# Output1-12.net
KiCad netlist of a schematic drawn in Altium Designer
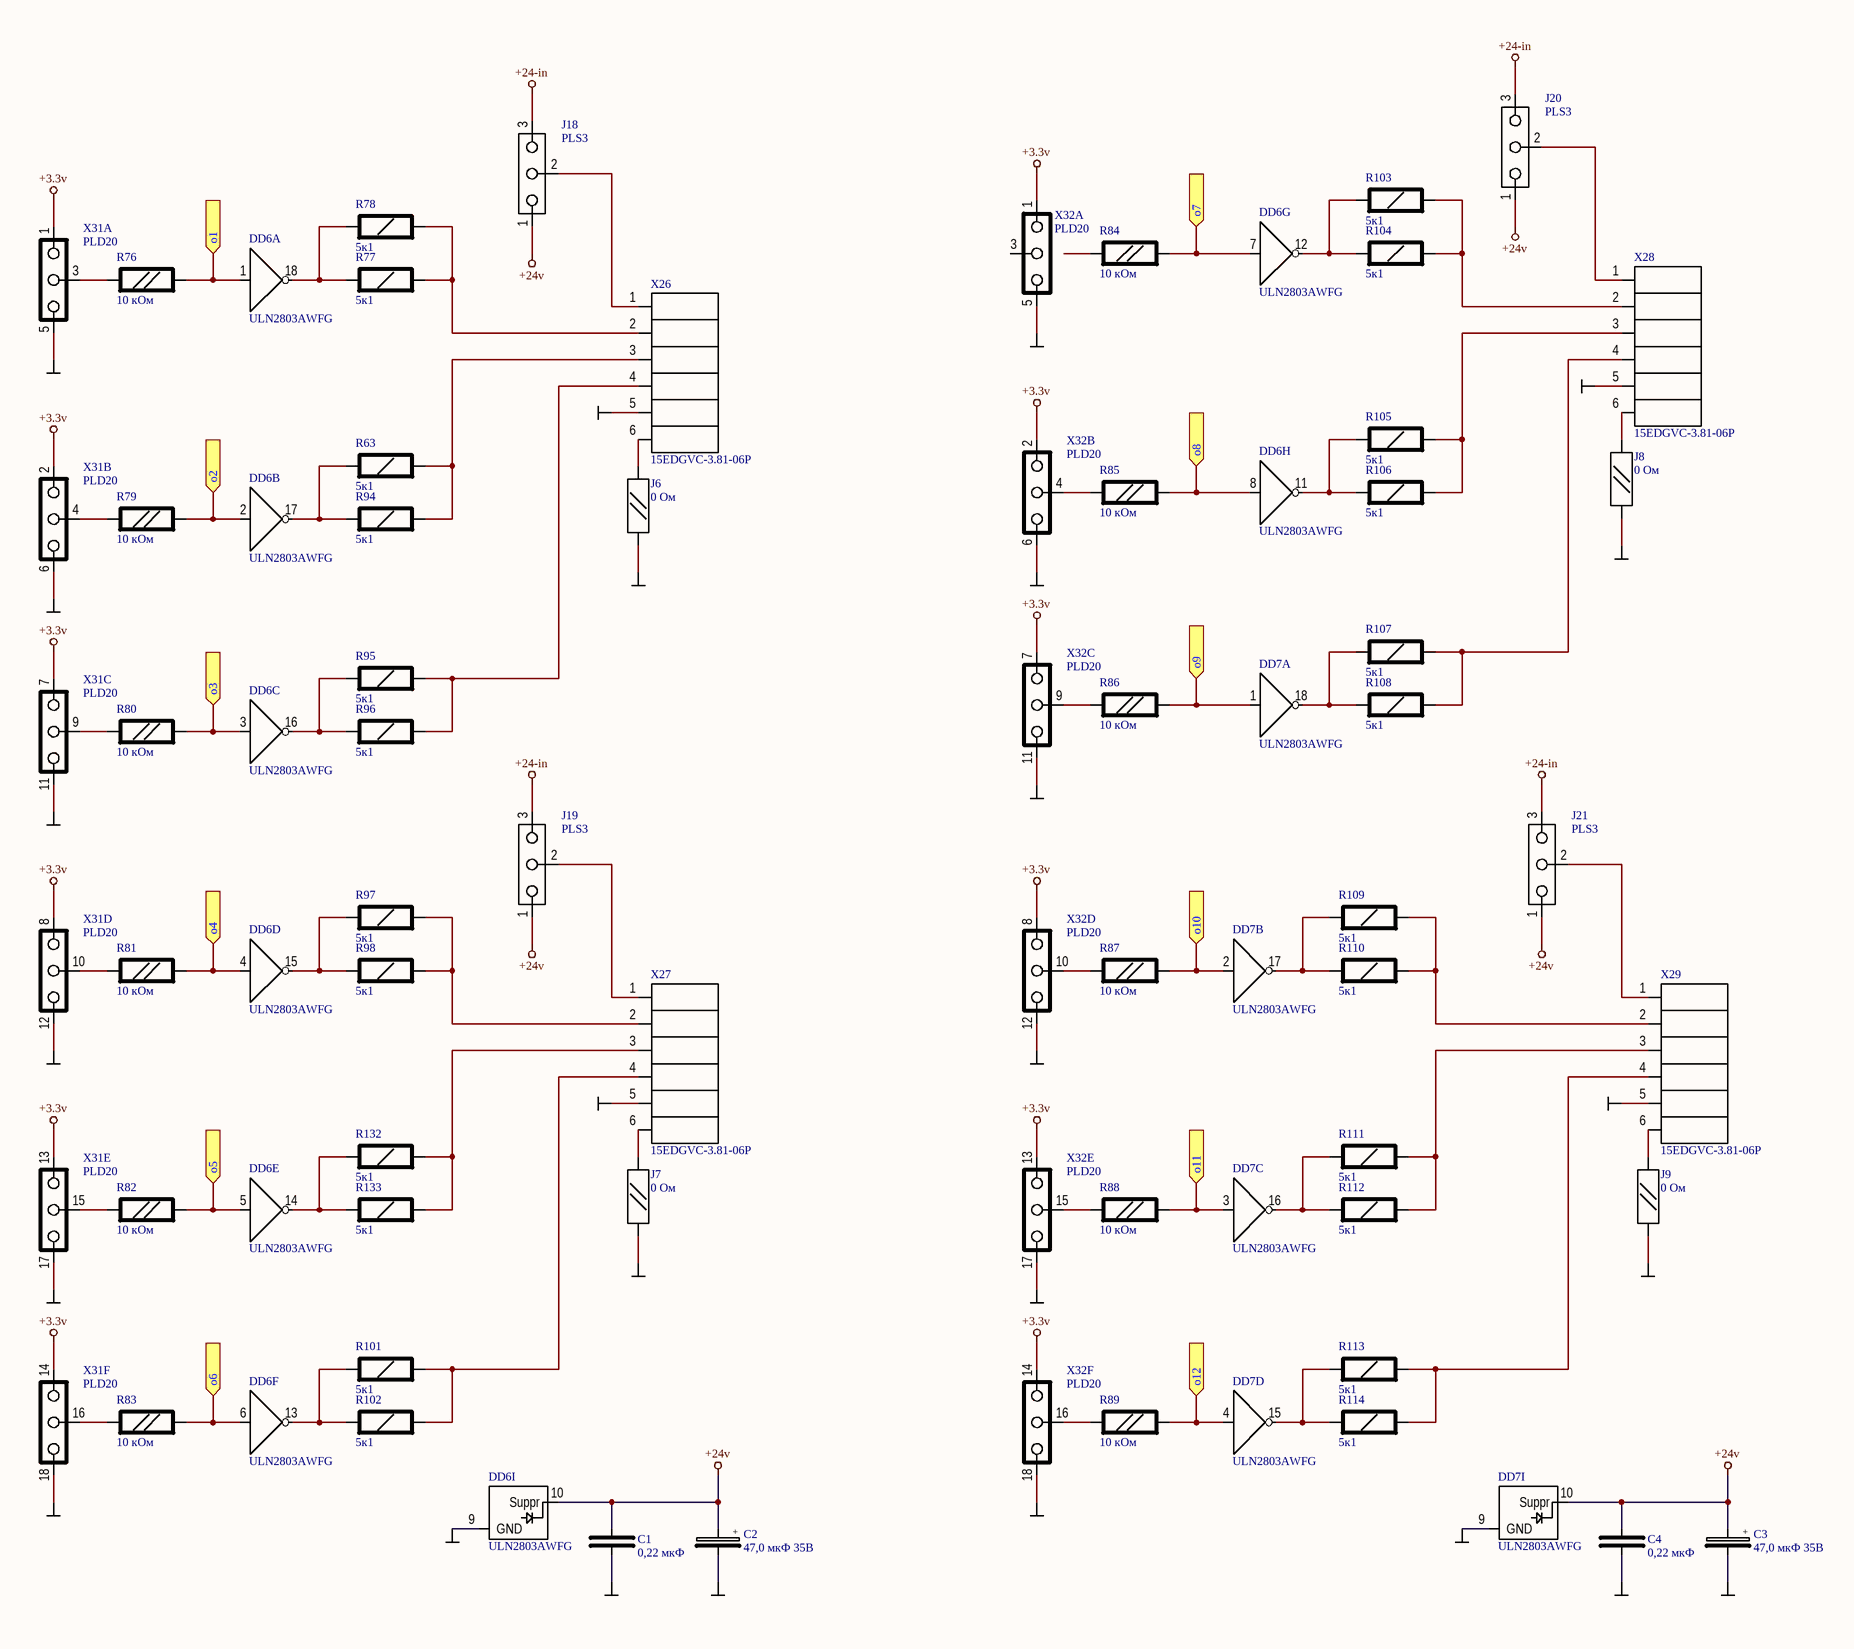
[diagram p0: Output1-12.SchDoc]

(export (version "E")
  (design (tool "Eeschema 10.0.6"))
  (components
    (comp (ref "C1")
      (value "0,22 мкФ")
      (footprint "SMD0805CAP")
      (description "Чип конденсатор 0805")
      (fields (field (name "VOLTAGE") "50V"))
      (libsource (lib "SL02_22F") (part "C0805"))
    )
    (comp (ref "C2")
      (value "47,0 мкФ 35В")
      (footprint "cap6")
      (description "5мм Электролитический конденсатор")
      (libsource (lib "SL02_22F") (part "C_e"))
    )
    (comp (ref "C3")
      (value "47,0 мкФ 35В")
      (footprint "cap6")
      (description "5мм Электролитический конденсатор")
      (libsource (lib "SL02_22F") (part "C_e"))
    )
    (comp (ref "C4")
      (value "0,22 мкФ")
      (footprint "SMD0805CAP")
      (description "Чип конденсатор 0805")
      (fields (field (name "VOLTAGE") "50V"))
      (libsource (lib "SL02_22F") (part "C0805"))
    )
    (comp (ref "DD6")
      (value "ULN2803AWFG")
      (footprint "SOL18")
      (description "Буфер 8-канальный")
      (fields (field (name "VOLTAGE") "50V"))
      (libsource (lib "SL02_22F") (part "ULN2803"))
    )
    (comp (ref "DD7")
      (value "ULN2803AWFG")
      (footprint "SOL18")
      (description "Буфер 8-канальный")
      (fields (field (name "VOLTAGE") "50V"))
      (libsource (lib "SL02_22F") (part "ULN2803"))
    )
    (comp (ref "J6")
      (value "0 Ом")
      (footprint "SMD0805RES")
      (description "SMD 0805 перемычка")
      (libsource (lib "L02_22F") (part "JR0805"))
    )
    (comp (ref "J7")
      (value "0 Ом")
      (footprint "SMD0805RES")
      (description "SMD 0805 перемычка")
      (libsource (lib "L02_22F") (part "JR0805"))
    )
    (comp (ref "J8")
      (value "0 Ом")
      (footprint "SMD0805RES")
      (description "SMD 0805 перемычка")
      (libsource (lib "L02_22F") (part "JR0805"))
    )
    (comp (ref "J9")
      (value "0 Ом")
      (footprint "SMD0805RES")
      (description "SMD 0805 перемычка")
      (libsource (lib "L02_22F") (part "JR0805"))
    )
    (comp (ref "J18")
      (value "PLS3")
      (footprint "HDR1X3")
      (description "Джампер PLS3 2.54мм")
      (libsource (lib "L02_22F") (part "PLS3"))
    )
    (comp (ref "J19")
      (value "PLS3")
      (footprint "HDR1X3")
      (description "Джампер PLS3 2.54мм")
      (libsource (lib "L02_22F") (part "PLS3"))
    )
    (comp (ref "J20")
      (value "PLS3")
      (footprint "HDR1X3")
      (description "Джампер PLS3 2.54мм")
      (libsource (lib "L02_22F") (part "PLS3"))
    )
    (comp (ref "J21")
      (value "PLS3")
      (footprint "HDR1X3")
      (description "Джампер PLS3 2.54мм")
      (libsource (lib "L02_22F") (part "PLS3"))
    )
    (comp (ref "R63")
      (value "5к1")
      (footprint "RES1206")
      (description "Чип резистор 1206")
      (fields (field (name "TOLERANCE") "5%"))
      (libsource (lib "SL02_22F") (part "R1206"))
    )
    (comp (ref "R76")
      (value "10 кОм")
      (footprint "SMD0805RES")
      (description "Чип резистор 0805")
      (fields (field (name "TOLERANCE") "5%"))
      (libsource (lib "SL02_22F") (part "R0805"))
    )
    (comp (ref "R77")
      (value "5к1")
      (footprint "RES1206")
      (description "Чип резистор 1206")
      (fields (field (name "TOLERANCE") "5%"))
      (libsource (lib "SL02_22F") (part "R1206"))
    )
    (comp (ref "R78")
      (value "5к1")
      (footprint "RES1206")
      (description "Чип резистор 1206")
      (fields (field (name "TOLERANCE") "5%"))
      (libsource (lib "SL02_22F") (part "R1206"))
    )
    (comp (ref "R79")
      (value "10 кОм")
      (footprint "SMD0805RES")
      (description "Чип резистор 0805")
      (fields (field (name "TOLERANCE") "5%"))
      (libsource (lib "SL02_22F") (part "R0805"))
    )
    (comp (ref "R80")
      (value "10 кОм")
      (footprint "SMD0805RES")
      (description "Чип резистор 0805")
      (fields (field (name "TOLERANCE") "5%"))
      (libsource (lib "SL02_22F") (part "R0805"))
    )
    (comp (ref "R81")
      (value "10 кОм")
      (footprint "SMD0805RES")
      (description "Чип резистор 0805")
      (fields (field (name "TOLERANCE") "5%"))
      (libsource (lib "SL02_22F") (part "R0805"))
    )
    (comp (ref "R82")
      (value "10 кОм")
      (footprint "SMD0805RES")
      (description "Чип резистор 0805")
      (fields (field (name "TOLERANCE") "5%"))
      (libsource (lib "SL02_22F") (part "R0805"))
    )
    (comp (ref "R83")
      (value "10 кОм")
      (footprint "SMD0805RES")
      (description "Чип резистор 0805")
      (fields (field (name "TOLERANCE") "5%"))
      (libsource (lib "SL02_22F") (part "R0805"))
    )
    (comp (ref "R84")
      (value "10 кОм")
      (footprint "SMD0805RES")
      (description "Чип резистор 0805")
      (fields (field (name "TOLERANCE") "5%"))
      (libsource (lib "SL02_22F") (part "R0805"))
    )
    (comp (ref "R85")
      (value "10 кОм")
      (footprint "SMD0805RES")
      (description "Чип резистор 0805")
      (fields (field (name "TOLERANCE") "5%"))
      (libsource (lib "SL02_22F") (part "R0805"))
    )
    (comp (ref "R86")
      (value "10 кОм")
      (footprint "SMD0805RES")
      (description "Чип резистор 0805")
      (fields (field (name "TOLERANCE") "5%"))
      (libsource (lib "SL02_22F") (part "R0805"))
    )
    (comp (ref "R87")
      (value "10 кОм")
      (footprint "SMD0805RES")
      (description "Чип резистор 0805")
      (fields (field (name "TOLERANCE") "5%"))
      (libsource (lib "SL02_22F") (part "R0805"))
    )
    (comp (ref "R88")
      (value "10 кОм")
      (footprint "SMD0805RES")
      (description "Чип резистор 0805")
      (fields (field (name "TOLERANCE") "5%"))
      (libsource (lib "SL02_22F") (part "R0805"))
    )
    (comp (ref "R89")
      (value "10 кОм")
      (footprint "SMD0805RES")
      (description "Чип резистор 0805")
      (fields (field (name "TOLERANCE") "5%"))
      (libsource (lib "SL02_22F") (part "R0805"))
    )
    (comp (ref "R94")
      (value "5к1")
      (footprint "RES1206")
      (description "Чип резистор 1206")
      (fields (field (name "TOLERANCE") "5%"))
      (libsource (lib "SL02_22F") (part "R1206"))
    )
    (comp (ref "R95")
      (value "5к1")
      (footprint "RES1206")
      (description "Чип резистор 1206")
      (fields (field (name "TOLERANCE") "5%"))
      (libsource (lib "SL02_22F") (part "R1206"))
    )
    (comp (ref "R96")
      (value "5к1")
      (footprint "RES1206")
      (description "Чип резистор 1206")
      (fields (field (name "TOLERANCE") "5%"))
      (libsource (lib "SL02_22F") (part "R1206"))
    )
    (comp (ref "R97")
      (value "5к1")
      (footprint "RES1206")
      (description "Чип резистор 1206")
      (fields (field (name "TOLERANCE") "5%"))
      (libsource (lib "SL02_22F") (part "R1206"))
    )
    (comp (ref "R98")
      (value "5к1")
      (footprint "RES1206")
      (description "Чип резистор 1206")
      (fields (field (name "TOLERANCE") "5%"))
      (libsource (lib "SL02_22F") (part "R1206"))
    )
    (comp (ref "R101")
      (value "5к1")
      (footprint "RES1206")
      (description "Чип резистор 1206")
      (fields (field (name "TOLERANCE") "5%"))
      (libsource (lib "SL02_22F") (part "R1206"))
    )
    (comp (ref "R102")
      (value "5к1")
      (footprint "RES1206")
      (description "Чип резистор 1206")
      (fields (field (name "TOLERANCE") "5%"))
      (libsource (lib "SL02_22F") (part "R1206"))
    )
    (comp (ref "R103")
      (value "5к1")
      (footprint "RES1206")
      (description "Чип резистор 1206")
      (fields (field (name "TOLERANCE") "5%"))
      (libsource (lib "SL02_22F") (part "R1206"))
    )
    (comp (ref "R104")
      (value "5к1")
      (footprint "RES1206")
      (description "Чип резистор 1206")
      (fields (field (name "TOLERANCE") "5%"))
      (libsource (lib "SL02_22F") (part "R1206"))
    )
    (comp (ref "R105")
      (value "5к1")
      (footprint "RES1206")
      (description "Чип резистор 1206")
      (fields (field (name "TOLERANCE") "5%"))
      (libsource (lib "SL02_22F") (part "R1206"))
    )
    (comp (ref "R106")
      (value "5к1")
      (footprint "RES1206")
      (description "Чип резистор 1206")
      (fields (field (name "TOLERANCE") "5%"))
      (libsource (lib "SL02_22F") (part "R1206"))
    )
    (comp (ref "R107")
      (value "5к1")
      (footprint "RES1206")
      (description "Чип резистор 1206")
      (fields (field (name "TOLERANCE") "5%"))
      (libsource (lib "SL02_22F") (part "R1206"))
    )
    (comp (ref "R108")
      (value "5к1")
      (footprint "RES1206")
      (description "Чип резистор 1206")
      (fields (field (name "TOLERANCE") "5%"))
      (libsource (lib "SL02_22F") (part "R1206"))
    )
    (comp (ref "R109")
      (value "5к1")
      (footprint "RES1206")
      (description "Чип резистор 1206")
      (fields (field (name "TOLERANCE") "5%"))
      (libsource (lib "SL02_22F") (part "R1206"))
    )
    (comp (ref "R110")
      (value "5к1")
      (footprint "RES1206")
      (description "Чип резистор 1206")
      (fields (field (name "TOLERANCE") "5%"))
      (libsource (lib "SL02_22F") (part "R1206"))
    )
    (comp (ref "R111")
      (value "5к1")
      (footprint "RES1206")
      (description "Чип резистор 1206")
      (fields (field (name "TOLERANCE") "5%"))
      (libsource (lib "SL02_22F") (part "R1206"))
    )
    (comp (ref "R112")
      (value "5к1")
      (footprint "RES1206")
      (description "Чип резистор 1206")
      (fields (field (name "TOLERANCE") "5%"))
      (libsource (lib "SL02_22F") (part "R1206"))
    )
    (comp (ref "R113")
      (value "5к1")
      (footprint "RES1206")
      (description "Чип резистор 1206")
      (fields (field (name "TOLERANCE") "5%"))
      (libsource (lib "SL02_22F") (part "R1206"))
    )
    (comp (ref "R114")
      (value "5к1")
      (footprint "RES1206")
      (description "Чип резистор 1206")
      (fields (field (name "TOLERANCE") "5%"))
      (libsource (lib "SL02_22F") (part "R1206"))
    )
    (comp (ref "R132")
      (value "5к1")
      (footprint "RES1206")
      (description "Чип резистор 1206")
      (fields (field (name "TOLERANCE") "5%"))
      (libsource (lib "SL02_22F") (part "R1206"))
    )
    (comp (ref "R133")
      (value "5к1")
      (footprint "RES1206")
      (description "Чип резистор 1206")
      (fields (field (name "TOLERANCE") "5%"))
      (libsource (lib "SL02_22F") (part "R1206"))
    )
    (comp (ref "X26")
      (value "15EDGVC-3.81-06P")
      (footprint "15EDGVC_081_6")
      (description "Вилка  6/3.81")
      (fields (field (name "VOLTAGE") "2кВ"))
      (libsource (lib "L02_22F") (part "15EDGVC-3.81-06P"))
    )
    (comp (ref "X27")
      (value "15EDGVC-3.81-06P")
      (footprint "15EDGVC_081_6")
      (description "Вилка  6/3.81")
      (fields (field (name "VOLTAGE") "2кВ"))
      (libsource (lib "L02_22F") (part "15EDGVC-3.81-06P"))
    )
    (comp (ref "X28")
      (value "15EDGVC-3.81-06P")
      (footprint "15EDGVC_081_6")
      (description "Вилка  6/3.81")
      (fields (field (name "VOLTAGE") "2кВ"))
      (libsource (lib "L02_22F") (part "15EDGVC-3.81-06P"))
    )
    (comp (ref "X29")
      (value "15EDGVC-3.81-06P")
      (footprint "15EDGVC_081_6")
      (description "Вилка  6/3.81")
      (fields (field (name "VOLTAGE") "2кВ"))
      (libsource (lib "L02_22F") (part "15EDGVC-3.81-06P"))
    )
    (comp (ref "X31")
      (value "PLD20")
      (footprint "pld2x10_1.27")
      (description "Вилка  PLD 20/1.27")
      (libsource (lib "") (part "PLD20_2"))
    )
    (comp (ref "X32")
      (value "PLD20")
      (footprint "pld2x10_1.27")
      (description "Вилка  PLD 20/1.27")
      (libsource (lib "") (part "PLD20_1"))
    )
  )
  (nets
    (net (code "1") (name "+3.3v") (class "Default")
      (node (ref "X31") (pin "1") (pinfunction "1_1") (pintype "passive"))
      (node (ref "X31") (pin "13") (pinfunction "13_13") (pintype "passive"))
      (node (ref "X31") (pin "14") (pinfunction "14_14") (pintype "passive"))
      (node (ref "X31") (pin "2") (pinfunction "2_2") (pintype "passive"))
      (node (ref "X31") (pin "7") (pinfunction "7_7") (pintype "passive"))
      (node (ref "X31") (pin "8") (pinfunction "8_8") (pintype "passive"))
      (node (ref "X32") (pin "1") (pinfunction "1_1") (pintype "passive"))
      (node (ref "X32") (pin "13") (pinfunction "13_13") (pintype "passive"))
      (node (ref "X32") (pin "14") (pinfunction "14_14") (pintype "passive"))
      (node (ref "X32") (pin "2") (pinfunction "2_2") (pintype "passive"))
      (node (ref "X32") (pin "7") (pinfunction "7_7") (pintype "passive"))
      (node (ref "X32") (pin "8") (pinfunction "8_8") (pintype "passive"))
    )
    (net (code "2") (name "+24-in") (class "Default")
      (node (ref "J18") (pin "3") (pinfunction "Left_3") (pintype "passive"))
      (node (ref "J19") (pin "3") (pinfunction "Left_3") (pintype "passive"))
      (node (ref "J20") (pin "3") (pinfunction "Left_3") (pintype "passive"))
      (node (ref "J21") (pin "3") (pinfunction "Left_3") (pintype "passive"))
    )
    (net (code "3") (name "+24v") (class "Default")
      (node (ref "C1") (pin "1") (pinfunction "1_1") (pintype "passive"))
      (node (ref "C2") (pin "1") (pinfunction "+_1") (pintype "passive"))
      (node (ref "C3") (pin "1") (pinfunction "+_1") (pintype "passive"))
      (node (ref "C4") (pin "1") (pinfunction "1_1") (pintype "passive"))
      (node (ref "DD6") (pin "10") (pinfunction "Suppr_10") (pintype "passive"))
      (node (ref "DD7") (pin "10") (pinfunction "Suppr_10") (pintype "passive"))
      (node (ref "J18") (pin "1") (pinfunction "Right_1") (pintype "passive"))
      (node (ref "J19") (pin "1") (pinfunction "Right_1") (pintype "passive"))
      (node (ref "J20") (pin "1") (pinfunction "Right_1") (pintype "passive"))
      (node (ref "J21") (pin "1") (pinfunction "Right_1") (pintype "passive"))
    )
    (net (code "4") (name "/o1") (class "Default")
      (node (ref "DD6") (pin "1") (pinfunction "In_1") (pintype "input"))
      (node (ref "R76") (pin "1") (pinfunction "1_1") (pintype "passive"))
    )
    (net (code "5") (name "/o2") (class "Default")
      (node (ref "DD6") (pin "2") (pinfunction "In_2") (pintype "input"))
      (node (ref "R79") (pin "1") (pinfunction "1_1") (pintype "passive"))
    )
    (net (code "6") (name "/o3") (class "Default")
      (node (ref "DD6") (pin "3") (pinfunction "In_3") (pintype "input"))
      (node (ref "R80") (pin "1") (pinfunction "1_1") (pintype "passive"))
    )
    (net (code "7") (name "/o4") (class "Default")
      (node (ref "DD6") (pin "4") (pinfunction "In_4") (pintype "input"))
      (node (ref "R81") (pin "1") (pinfunction "1_1") (pintype "passive"))
    )
    (net (code "8") (name "/o5") (class "Default")
      (node (ref "DD6") (pin "5") (pinfunction "In_5") (pintype "input"))
      (node (ref "R82") (pin "1") (pinfunction "1_1") (pintype "passive"))
    )
    (net (code "9") (name "/o6") (class "Default")
      (node (ref "DD6") (pin "6") (pinfunction "In_6") (pintype "input"))
      (node (ref "R83") (pin "1") (pinfunction "1_1") (pintype "passive"))
    )
    (net (code "10") (name "/o7") (class "Default")
      (node (ref "DD6") (pin "7") (pinfunction "In_7") (pintype "input"))
      (node (ref "R84") (pin "1") (pinfunction "1_1") (pintype "passive"))
    )
    (net (code "11") (name "/o8") (class "Default")
      (node (ref "DD6") (pin "8") (pinfunction "In_8") (pintype "input"))
      (node (ref "R85") (pin "1") (pinfunction "1_1") (pintype "passive"))
    )
    (net (code "12") (name "/o9") (class "Default")
      (node (ref "DD7") (pin "1") (pinfunction "In_1") (pintype "input"))
      (node (ref "R86") (pin "1") (pinfunction "1_1") (pintype "passive"))
    )
    (net (code "13") (name "/o10") (class "Default")
      (node (ref "DD7") (pin "2") (pinfunction "In_2") (pintype "input"))
      (node (ref "R87") (pin "1") (pinfunction "1_1") (pintype "passive"))
    )
    (net (code "14") (name "/o11") (class "Default")
      (node (ref "DD7") (pin "3") (pinfunction "In_3") (pintype "input"))
      (node (ref "R88") (pin "1") (pinfunction "1_1") (pintype "passive"))
    )
    (net (code "15") (name "/o12") (class "Default")
      (node (ref "DD7") (pin "4") (pinfunction "In_4") (pintype "input"))
      (node (ref "R89") (pin "1") (pinfunction "1_1") (pintype "passive"))
    )
    (net (code "16") (name "GND") (class "Default")
      (node (ref "C1") (pin "2") (pinfunction "2_2") (pintype "passive"))
      (node (ref "C2") (pin "2") (pinfunction "-_2") (pintype "passive"))
      (node (ref "C3") (pin "2") (pinfunction "-_2") (pintype "passive"))
      (node (ref "C4") (pin "2") (pinfunction "2_2") (pintype "passive"))
      (node (ref "DD6") (pin "9") (pinfunction "GND_9") (pintype "passive"))
      (node (ref "DD7") (pin "9") (pinfunction "GND_9") (pintype "passive"))
      (node (ref "J6") (pin "2") (pinfunction "2_2") (pintype "passive"))
      (node (ref "J7") (pin "2") (pinfunction "2_2") (pintype "passive"))
      (node (ref "J8") (pin "2") (pinfunction "2_2") (pintype "passive"))
      (node (ref "J9") (pin "2") (pinfunction "2_2") (pintype "passive"))
      (node (ref "X26") (pin "5") (pinfunction "5_5") (pintype "passive"))
      (node (ref "X27") (pin "5") (pinfunction "5_5") (pintype "passive"))
      (node (ref "X28") (pin "5") (pinfunction "5_5") (pintype "passive"))
      (node (ref "X29") (pin "5") (pinfunction "5_5") (pintype "passive"))
      (node (ref "X31") (pin "11") (pinfunction "11_11") (pintype "passive"))
      (node (ref "X31") (pin "12") (pinfunction "12_12") (pintype "passive"))
      (node (ref "X31") (pin "17") (pinfunction "17_17") (pintype "passive"))
      (node (ref "X31") (pin "18") (pinfunction "18_18") (pintype "passive"))
      (node (ref "X31") (pin "5") (pinfunction "5_5") (pintype "passive"))
      (node (ref "X31") (pin "6") (pinfunction "6_6") (pintype "passive"))
      (node (ref "X32") (pin "11") (pinfunction "11_11") (pintype "passive"))
      (node (ref "X32") (pin "12") (pinfunction "12_12") (pintype "passive"))
      (node (ref "X32") (pin "17") (pinfunction "17_17") (pintype "passive"))
      (node (ref "X32") (pin "18") (pinfunction "18_18") (pintype "passive"))
      (node (ref "X32") (pin "5") (pinfunction "5_5") (pintype "passive"))
      (node (ref "X32") (pin "6") (pinfunction "6_6") (pintype "passive"))
    )
    (net (code "17") (name "Net-(DD6A-OUT)") (class "Default")
      (node (ref "DD6") (pin "18") (pinfunction "OUT_18") (pintype "output"))
      (node (ref "R77") (pin "2") (pinfunction "2_2") (pintype "passive"))
      (node (ref "R78") (pin "2") (pinfunction "2_2") (pintype "passive"))
    )
    (net (code "18") (name "Net-(DD6B-OUT)") (class "Default")
      (node (ref "DD6") (pin "17") (pinfunction "OUT_17") (pintype "output"))
      (node (ref "R63") (pin "2") (pinfunction "2_2") (pintype "passive"))
      (node (ref "R94") (pin "2") (pinfunction "2_2") (pintype "passive"))
    )
    (net (code "19") (name "Net-(DD6C-OUT)") (class "Default")
      (node (ref "DD6") (pin "16") (pinfunction "OUT_16") (pintype "output"))
      (node (ref "R95") (pin "2") (pinfunction "2_2") (pintype "passive"))
      (node (ref "R96") (pin "2") (pinfunction "2_2") (pintype "passive"))
    )
    (net (code "20") (name "Net-(DD6D-OUT)") (class "Default")
      (node (ref "DD6") (pin "15") (pinfunction "OUT_15") (pintype "output"))
      (node (ref "R97") (pin "2") (pinfunction "2_2") (pintype "passive"))
      (node (ref "R98") (pin "2") (pinfunction "2_2") (pintype "passive"))
    )
    (net (code "21") (name "Net-(DD6E-OUT)") (class "Default")
      (node (ref "DD6") (pin "14") (pinfunction "OUT_14") (pintype "output"))
      (node (ref "R132") (pin "2") (pinfunction "2_2") (pintype "passive"))
      (node (ref "R133") (pin "2") (pinfunction "2_2") (pintype "passive"))
    )
    (net (code "22") (name "Net-(DD6F-OUT)") (class "Default")
      (node (ref "DD6") (pin "13") (pinfunction "OUT_13") (pintype "output"))
      (node (ref "R101") (pin "2") (pinfunction "2_2") (pintype "passive"))
      (node (ref "R102") (pin "2") (pinfunction "2_2") (pintype "passive"))
    )
    (net (code "23") (name "Net-(DD6G-OUT)") (class "Default")
      (node (ref "DD6") (pin "12") (pinfunction "OUT_12") (pintype "output"))
      (node (ref "R103") (pin "2") (pinfunction "2_2") (pintype "passive"))
      (node (ref "R104") (pin "2") (pinfunction "2_2") (pintype "passive"))
    )
    (net (code "24") (name "Net-(DD6H-OUT)") (class "Default")
      (node (ref "DD6") (pin "11") (pinfunction "OUT_11") (pintype "output"))
      (node (ref "R105") (pin "2") (pinfunction "2_2") (pintype "passive"))
      (node (ref "R106") (pin "2") (pinfunction "2_2") (pintype "passive"))
    )
    (net (code "25") (name "Net-(DD7A-OUT)") (class "Default")
      (node (ref "DD7") (pin "18") (pinfunction "OUT_18") (pintype "output"))
      (node (ref "R107") (pin "2") (pinfunction "2_2") (pintype "passive"))
      (node (ref "R108") (pin "2") (pinfunction "2_2") (pintype "passive"))
    )
    (net (code "26") (name "Net-(DD7B-OUT)") (class "Default")
      (node (ref "DD7") (pin "17") (pinfunction "OUT_17") (pintype "output"))
      (node (ref "R109") (pin "2") (pinfunction "2_2") (pintype "passive"))
      (node (ref "R110") (pin "2") (pinfunction "2_2") (pintype "passive"))
    )
    (net (code "27") (name "Net-(DD7C-OUT)") (class "Default")
      (node (ref "DD7") (pin "16") (pinfunction "OUT_16") (pintype "output"))
      (node (ref "R111") (pin "2") (pinfunction "2_2") (pintype "passive"))
      (node (ref "R112") (pin "2") (pinfunction "2_2") (pintype "passive"))
    )
    (net (code "28") (name "Net-(DD7D-OUT)") (class "Default")
      (node (ref "DD7") (pin "15") (pinfunction "OUT_15") (pintype "output"))
      (node (ref "R113") (pin "2") (pinfunction "2_2") (pintype "passive"))
      (node (ref "R114") (pin "2") (pinfunction "2_2") (pintype "passive"))
    )
    (net (code "29") (name "Net-(J6-Pad1)") (class "Default")
      (node (ref "J6") (pin "1") (pinfunction "1_1") (pintype "passive"))
      (node (ref "X26") (pin "6") (pinfunction "6_6") (pintype "passive"))
    )
    (net (code "30") (name "Net-(J7-Pad1)") (class "Default")
      (node (ref "J7") (pin "1") (pinfunction "1_1") (pintype "passive"))
      (node (ref "X27") (pin "6") (pinfunction "6_6") (pintype "passive"))
    )
    (net (code "31") (name "Net-(J8-Pad1)") (class "Default")
      (node (ref "J8") (pin "1") (pinfunction "1_1") (pintype "passive"))
      (node (ref "X28") (pin "6") (pinfunction "6_6") (pintype "passive"))
    )
    (net (code "32") (name "Net-(J9-Pad1)") (class "Default")
      (node (ref "J9") (pin "1") (pinfunction "1_1") (pintype "passive"))
      (node (ref "X29") (pin "6") (pinfunction "6_6") (pintype "passive"))
    )
    (net (code "33") (name "Net-(J18-Cetnter)") (class "Default")
      (node (ref "J18") (pin "2") (pinfunction "Cetnter_2") (pintype "passive"))
      (node (ref "X26") (pin "1") (pinfunction "1_1") (pintype "passive"))
    )
    (net (code "34") (name "Net-(J19-Cetnter)") (class "Default")
      (node (ref "J19") (pin "2") (pinfunction "Cetnter_2") (pintype "passive"))
      (node (ref "X27") (pin "1") (pinfunction "1_1") (pintype "passive"))
    )
    (net (code "35") (name "Net-(J20-Cetnter)") (class "Default")
      (node (ref "J20") (pin "2") (pinfunction "Cetnter_2") (pintype "passive"))
      (node (ref "X28") (pin "1") (pinfunction "1_1") (pintype "passive"))
    )
    (net (code "36") (name "Net-(J21-Cetnter)") (class "Default")
      (node (ref "J21") (pin "2") (pinfunction "Cetnter_2") (pintype "passive"))
      (node (ref "X29") (pin "1") (pinfunction "1_1") (pintype "passive"))
    )
    (net (code "37") (name "Net-(R63-Pad1)") (class "Default")
      (node (ref "R63") (pin "1") (pinfunction "1_1") (pintype "passive"))
      (node (ref "R94") (pin "1") (pinfunction "1_1") (pintype "passive"))
      (node (ref "X26") (pin "3") (pinfunction "3_3") (pintype "passive"))
    )
    (net (code "38") (name "Net-(R76-Pad2)") (class "Default")
      (node (ref "R76") (pin "2") (pinfunction "2_2") (pintype "passive"))
      (node (ref "X31") (pin "3") (pinfunction "3_3") (pintype "passive"))
    )
    (net (code "39") (name "Net-(R77-Pad1)") (class "Default")
      (node (ref "R77") (pin "1") (pinfunction "1_1") (pintype "passive"))
      (node (ref "R78") (pin "1") (pinfunction "1_1") (pintype "passive"))
      (node (ref "X26") (pin "2") (pinfunction "2_2") (pintype "passive"))
    )
    (net (code "40") (name "Net-(R79-Pad2)") (class "Default")
      (node (ref "R79") (pin "2") (pinfunction "2_2") (pintype "passive"))
      (node (ref "X31") (pin "4") (pinfunction "4_4") (pintype "passive"))
    )
    (net (code "41") (name "Net-(R80-Pad2)") (class "Default")
      (node (ref "R80") (pin "2") (pinfunction "2_2") (pintype "passive"))
      (node (ref "X31") (pin "9") (pinfunction "9_9") (pintype "passive"))
    )
    (net (code "42") (name "Net-(R81-Pad2)") (class "Default")
      (node (ref "R81") (pin "2") (pinfunction "2_2") (pintype "passive"))
      (node (ref "X31") (pin "10") (pinfunction "10_10") (pintype "passive"))
    )
    (net (code "43") (name "Net-(R82-Pad2)") (class "Default")
      (node (ref "R82") (pin "2") (pinfunction "2_2") (pintype "passive"))
      (node (ref "X31") (pin "15") (pinfunction "15_15") (pintype "passive"))
    )
    (net (code "44") (name "Net-(R83-Pad2)") (class "Default")
      (node (ref "R83") (pin "2") (pinfunction "2_2") (pintype "passive"))
      (node (ref "X31") (pin "16") (pinfunction "16_16") (pintype "passive"))
    )
    (net (code "45") (name "Net-(R85-Pad2)") (class "Default")
      (node (ref "R85") (pin "2") (pinfunction "2_2") (pintype "passive"))
      (node (ref "X32") (pin "4") (pinfunction "4_4") (pintype "passive"))
    )
    (net (code "46") (name "Net-(R86-Pad2)") (class "Default")
      (node (ref "R86") (pin "2") (pinfunction "2_2") (pintype "passive"))
      (node (ref "X32") (pin "9") (pinfunction "9_9") (pintype "passive"))
    )
    (net (code "47") (name "Net-(R87-Pad2)") (class "Default")
      (node (ref "R87") (pin "2") (pinfunction "2_2") (pintype "passive"))
      (node (ref "X32") (pin "10") (pinfunction "10_10") (pintype "passive"))
    )
    (net (code "48") (name "Net-(R88-Pad2)") (class "Default")
      (node (ref "R88") (pin "2") (pinfunction "2_2") (pintype "passive"))
      (node (ref "X32") (pin "15") (pinfunction "15_15") (pintype "passive"))
    )
    (net (code "49") (name "Net-(R89-Pad2)") (class "Default")
      (node (ref "R89") (pin "2") (pinfunction "2_2") (pintype "passive"))
      (node (ref "X32") (pin "16") (pinfunction "16_16") (pintype "passive"))
    )
    (net (code "50") (name "Net-(R95-Pad1)") (class "Default")
      (node (ref "R95") (pin "1") (pinfunction "1_1") (pintype "passive"))
      (node (ref "R96") (pin "1") (pinfunction "1_1") (pintype "passive"))
      (node (ref "X26") (pin "4") (pinfunction "4_4") (pintype "passive"))
    )
    (net (code "51") (name "Net-(R97-Pad1)") (class "Default")
      (node (ref "R97") (pin "1") (pinfunction "1_1") (pintype "passive"))
      (node (ref "R98") (pin "1") (pinfunction "1_1") (pintype "passive"))
      (node (ref "X27") (pin "2") (pinfunction "2_2") (pintype "passive"))
    )
    (net (code "52") (name "Net-(R101-Pad1)") (class "Default")
      (node (ref "R101") (pin "1") (pinfunction "1_1") (pintype "passive"))
      (node (ref "R102") (pin "1") (pinfunction "1_1") (pintype "passive"))
      (node (ref "X27") (pin "4") (pinfunction "4_4") (pintype "passive"))
    )
    (net (code "53") (name "Net-(R103-Pad1)") (class "Default")
      (node (ref "R103") (pin "1") (pinfunction "1_1") (pintype "passive"))
      (node (ref "R104") (pin "1") (pinfunction "1_1") (pintype "passive"))
      (node (ref "X28") (pin "2") (pinfunction "2_2") (pintype "passive"))
    )
    (net (code "54") (name "Net-(R105-Pad1)") (class "Default")
      (node (ref "R105") (pin "1") (pinfunction "1_1") (pintype "passive"))
      (node (ref "R106") (pin "1") (pinfunction "1_1") (pintype "passive"))
      (node (ref "X28") (pin "3") (pinfunction "3_3") (pintype "passive"))
    )
    (net (code "55") (name "Net-(R107-Pad1)") (class "Default")
      (node (ref "R107") (pin "1") (pinfunction "1_1") (pintype "passive"))
      (node (ref "R108") (pin "1") (pinfunction "1_1") (pintype "passive"))
      (node (ref "X28") (pin "4") (pinfunction "4_4") (pintype "passive"))
    )
    (net (code "56") (name "Net-(R109-Pad1)") (class "Default")
      (node (ref "R109") (pin "1") (pinfunction "1_1") (pintype "passive"))
      (node (ref "R110") (pin "1") (pinfunction "1_1") (pintype "passive"))
      (node (ref "X29") (pin "2") (pinfunction "2_2") (pintype "passive"))
    )
    (net (code "57") (name "Net-(R111-Pad1)") (class "Default")
      (node (ref "R111") (pin "1") (pinfunction "1_1") (pintype "passive"))
      (node (ref "R112") (pin "1") (pinfunction "1_1") (pintype "passive"))
      (node (ref "X29") (pin "3") (pinfunction "3_3") (pintype "passive"))
    )
    (net (code "58") (name "Net-(R113-Pad1)") (class "Default")
      (node (ref "R113") (pin "1") (pinfunction "1_1") (pintype "passive"))
      (node (ref "R114") (pin "1") (pinfunction "1_1") (pintype "passive"))
      (node (ref "X29") (pin "4") (pinfunction "4_4") (pintype "passive"))
    )
    (net (code "59") (name "Net-(R132-Pad1)") (class "Default")
      (node (ref "R132") (pin "1") (pinfunction "1_1") (pintype "passive"))
      (node (ref "R133") (pin "1") (pinfunction "1_1") (pintype "passive"))
      (node (ref "X27") (pin "3") (pinfunction "3_3") (pintype "passive"))
    )
    (net (code "60") (name "unconnected-(R84-Pad2)") (class "Default")
      (node (ref "R84") (pin "2") (pinfunction "2_2") (pintype "passive"))
    )
    (net (code "61") (name "unconnected-(X32-Pad3)") (class "Default")
      (node (ref "X32") (pin "3") (pinfunction "3_3") (pintype "passive"))
    )
  )
)
